# adc_board.net
KiCad netlist of a schematic drawn in EAGLE
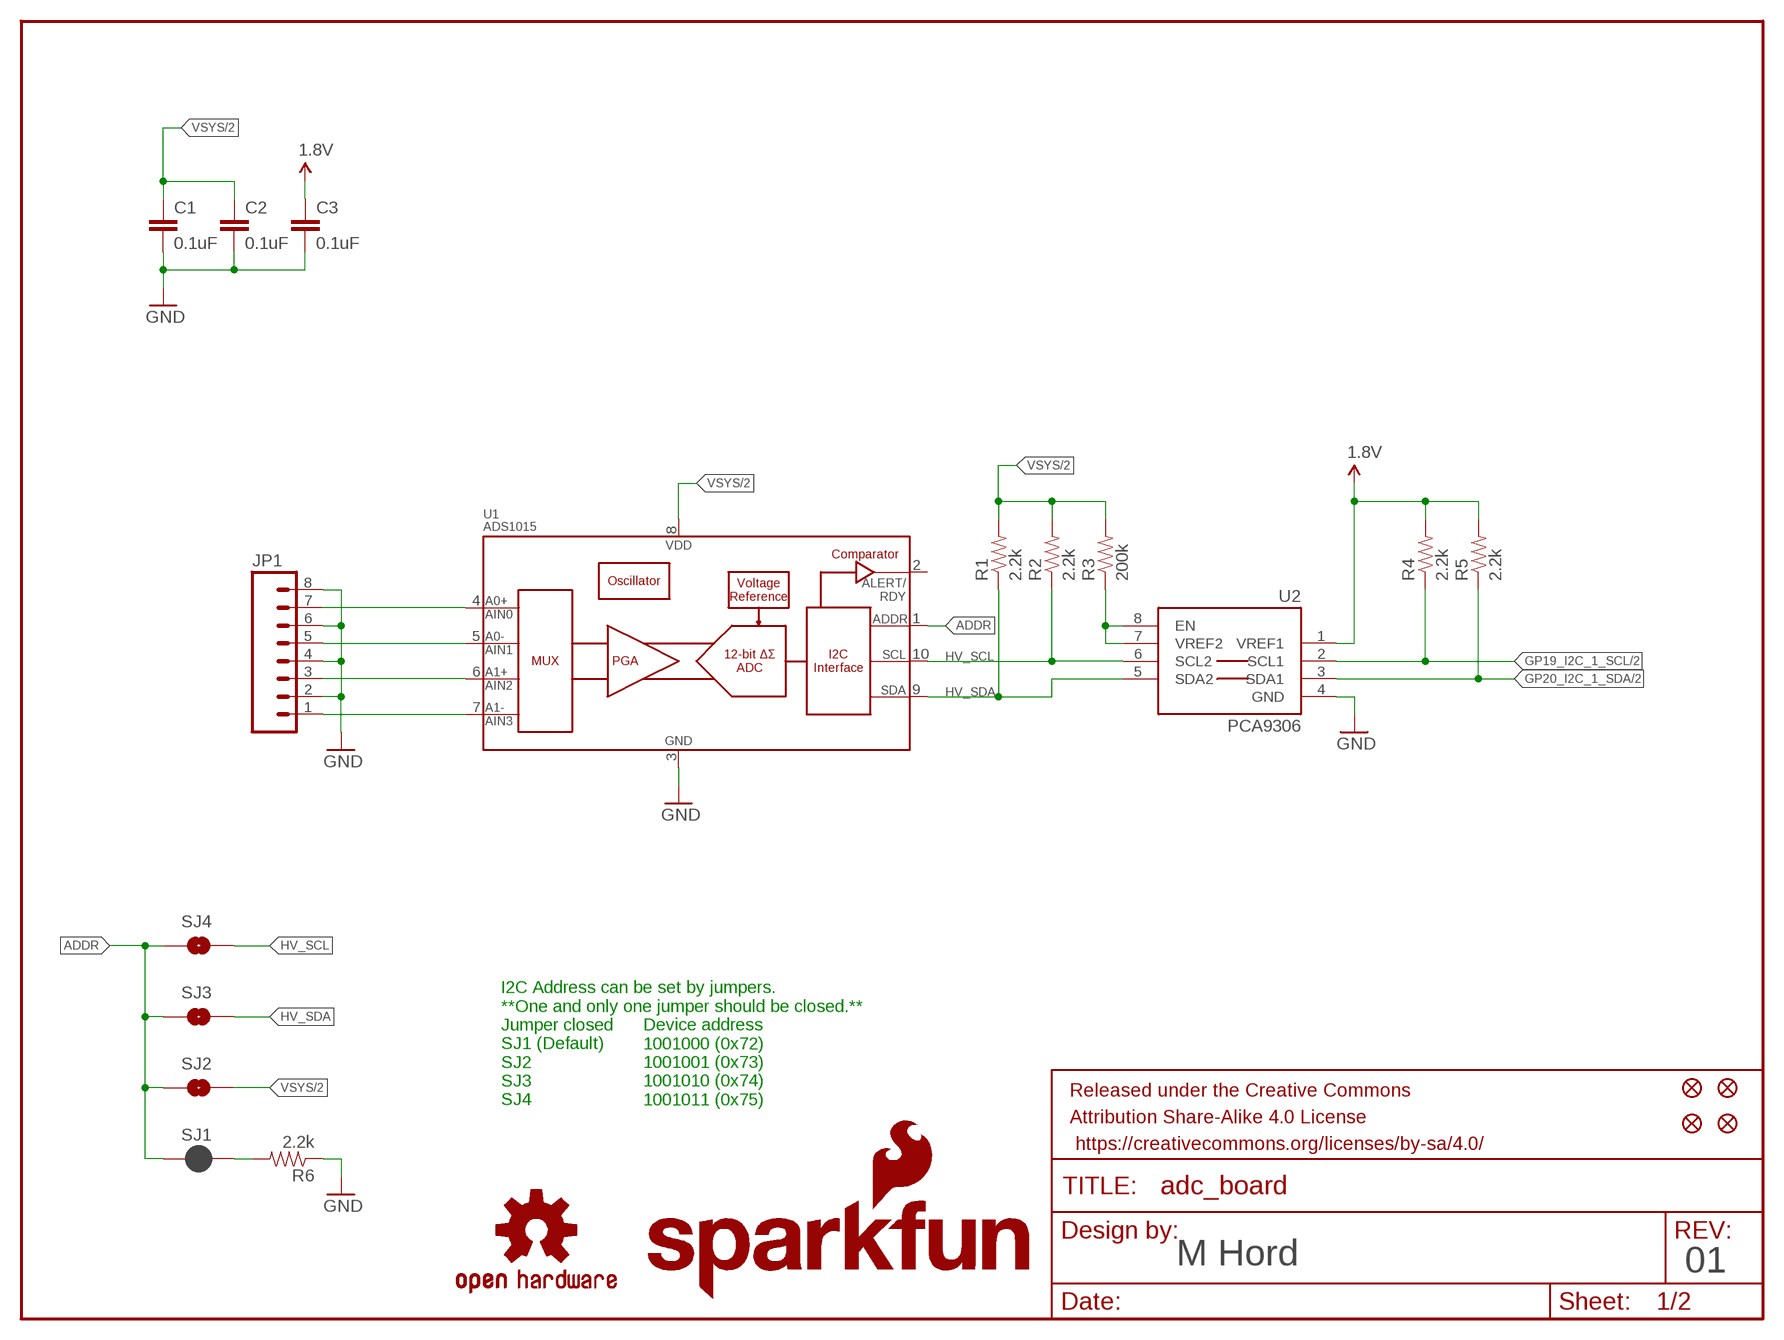
[diagram p0: schematic, sheet 1]
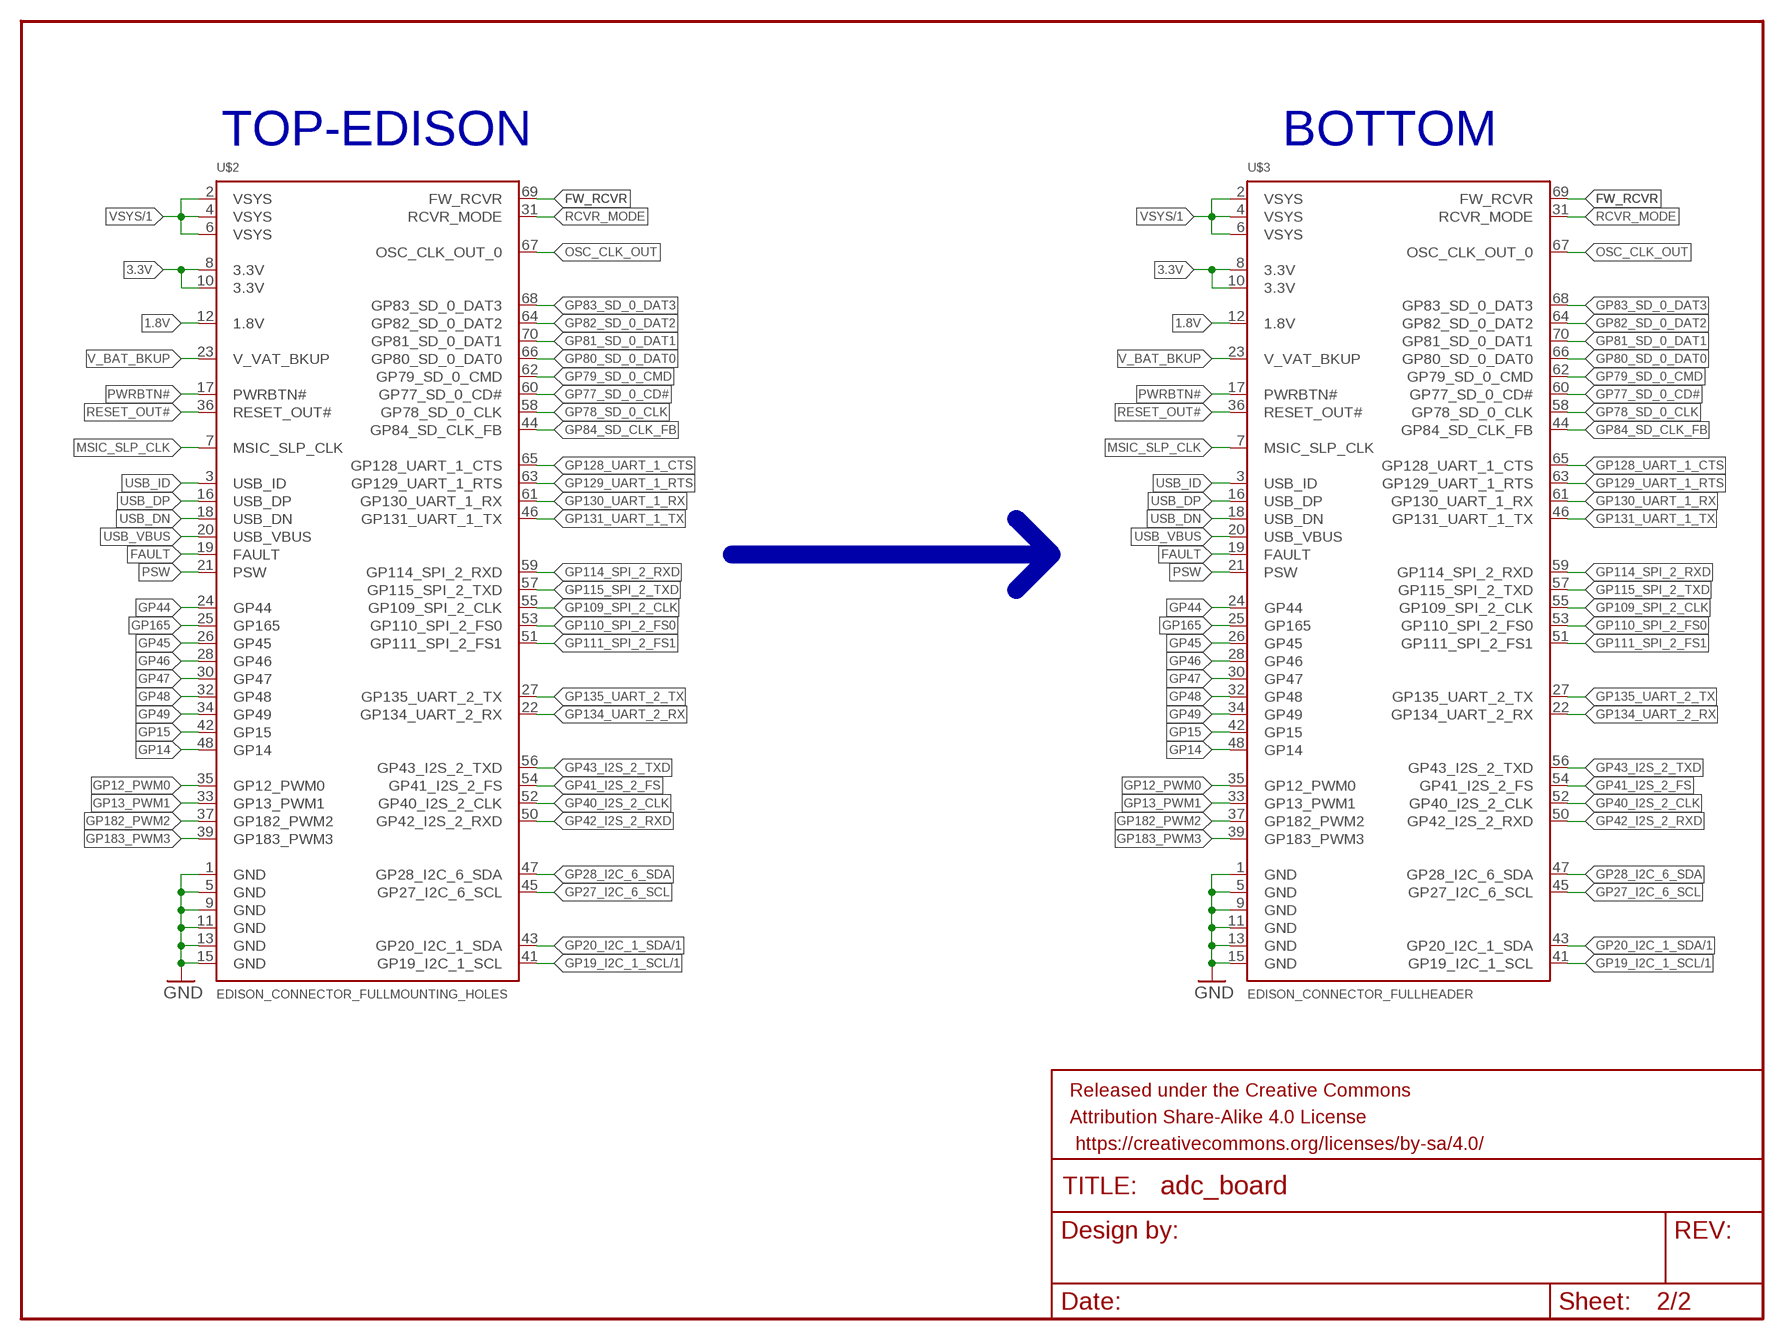
[diagram p1: schematic, sheet 2]

(export (version "E")
  (design (tool "Eeschema 10.0.6"))
  (components
    (comp (ref "C1")
      (value "0.1uF")
      (footprint "eagle-import:0603-CAP")
      (libsource (lib "eagle-import") (part "0.1UF-25V(+80/-20%)(0603)"))
    )
    (comp (ref "C2")
      (value "0.1uF")
      (footprint "eagle-import:0603-CAP")
      (libsource (lib "eagle-import") (part "0.1UF-25V(+80/-20%)(0603)"))
    )
    (comp (ref "C3")
      (value "0.1uF")
      (footprint "eagle-import:0603-CAP")
      (libsource (lib "eagle-import") (part "0.1UF-25V(+80/-20%)(0603)"))
    )
    (comp (ref "FID1")
      (value "FIDUCIAL1X2")
      (footprint "eagle-import:FIDUCIAL-1X2")
      (libsource (lib "eagle-import") (part "FIDUCIAL1X2"))
    )
    (comp (ref "FID2")
      (value "FIDUCIAL1X2")
      (footprint "eagle-import:FIDUCIAL-1X2")
      (libsource (lib "eagle-import") (part "FIDUCIAL1X2"))
    )
    (comp (ref "FID3")
      (value "FIDUCIAL1X2")
      (footprint "eagle-import:FIDUCIAL-1X2")
      (libsource (lib "eagle-import") (part "FIDUCIAL1X2"))
    )
    (comp (ref "FID4")
      (value "FIDUCIAL1X2")
      (footprint "eagle-import:FIDUCIAL-1X2")
      (libsource (lib "eagle-import") (part "FIDUCIAL1X2"))
    )
    (comp (ref "FRAME1")
      (value "FRAME-LETTER")
      (footprint "eagle-import:CREATIVE_COMMONS")
      (libsource (lib "eagle-import") (part "FRAME-LETTER"))
    )
    (comp (ref "JP1")
      (value "M081X08")
      (footprint "eagle-import:1X08")
      (libsource (lib "eagle-import") (part "M081X08"))
    )
    (comp (ref "LOGO1")
      (value "SFE_LOGO_NAME_FLAME.1_INCH")
      (footprint "eagle-import:SFE_LOGO_NAME_FLAME_.1")
      (libsource (lib "eagle-import") (part "SFE_LOGO_NAME_FLAME.1_INCH"))
    )
    (comp (ref "LOGO2")
      (value "OSHW-LOGOS")
      (footprint "eagle-import:OSHW-LOGO-S")
      (libsource (lib "eagle-import") (part "OSHW-LOGOS"))
    )
    (comp (ref "LOGO3")
      (value "SFE_LOGO_NAME_FLAME.1_INCH")
      (footprint "eagle-import:SFE_LOGO_NAME_FLAME_.1")
      (libsource (lib "eagle-import") (part "SFE_LOGO_NAME_FLAME.1_INCH"))
    )
    (comp (ref "LOGO4")
      (value "OSHW-LOGOS")
      (footprint "eagle-import:OSHW-LOGO-S")
      (libsource (lib "eagle-import") (part "OSHW-LOGOS"))
    )
    (comp (ref "R1")
      (value "2.2k")
      (footprint "eagle-import:0603-RES")
      (libsource (lib "eagle-import") (part "2.2KOHM1/10W1%(0603)"))
    )
    (comp (ref "R2")
      (value "2.2k")
      (footprint "eagle-import:0603-RES")
      (libsource (lib "eagle-import") (part "2.2KOHM1/10W1%(0603)"))
    )
    (comp (ref "R3")
      (value "200k")
      (footprint "eagle-import:0603-RES")
      (libsource (lib "eagle-import") (part "200KOHM1/10W1%(0603)200K"))
    )
    (comp (ref "R4")
      (value "2.2k")
      (footprint "eagle-import:0603-RES")
      (libsource (lib "eagle-import") (part "2.2KOHM1/10W1%(0603)"))
    )
    (comp (ref "R5")
      (value "2.2k")
      (footprint "eagle-import:0603-RES")
      (libsource (lib "eagle-import") (part "2.2KOHM1/10W1%(0603)"))
    )
    (comp (ref "R6")
      (value "2.2k")
      (footprint "eagle-import:0603-RES")
      (libsource (lib "eagle-import") (part "2.2KOHM1/10W1%(0603)"))
    )
    (comp (ref "SJ1")
      (value "JUMPER-PAD-2-NC_BY_PASTE")
      (footprint "eagle-import:PAD-JUMPER-2-NC_BY_PASTE_YES_SILK")
      (libsource (lib "eagle-import") (part "JUMPER-PAD-2-NC_BY_PASTE"))
    )
    (comp (ref "SJ2")
      (value "JUMPER-PAD-2-NOYES_SILK")
      (footprint "eagle-import:PAD-JUMPER-2-NO_YES_SILK")
      (libsource (lib "eagle-import") (part "JUMPER-PAD-2-NOYES_SILK"))
    )
    (comp (ref "SJ3")
      (value "JUMPER-PAD-2-NOYES_SILK")
      (footprint "eagle-import:PAD-JUMPER-2-NO_YES_SILK")
      (libsource (lib "eagle-import") (part "JUMPER-PAD-2-NOYES_SILK"))
    )
    (comp (ref "SJ4")
      (value "JUMPER-PAD-2-NOYES_SILK")
      (footprint "eagle-import:PAD-JUMPER-2-NO_YES_SILK")
      (libsource (lib "eagle-import") (part "JUMPER-PAD-2-NOYES_SILK"))
    )
    (comp (ref "U1")
      (value "ADS1015")
      (footprint "eagle-import:MSOP10")
      (libsource (lib "eagle-import") (part "ADS1015"))
    )
    (comp (ref "U2")
      (value "PCA9306")
      (footprint "eagle-import:PCA9306DC-1_1")
      (libsource (lib "eagle-import") (part "PCA9306PCA9306DC-1{colon}1"))
    )
    (comp (ref "FRAME2")
      (value "FRAME-LETTER")
      (footprint "eagle-import:CREATIVE_COMMONS")
      (libsource (lib "eagle-import") (part "FRAME-LETTER"))
    )
    (comp (ref "U$2")
      (value "EDISON_CONNECTOR_FULLMOUNTING_HOLES")
      (footprint "eagle-import:EDISON_DAUGHTER")
      (libsource (lib "eagle-import") (part "EDISON_CONNECTOR_FULLMOUNTING_HOLES"))
    )
    (comp (ref "U$3")
      (value "EDISON_CONNECTOR_FULLHEADER")
      (footprint "eagle-import:DF40C-70DP-0.4(51)")
      (libsource (lib "eagle-import") (part "EDISON_CONNECTOR_FULLHEADER"))
    )
  )
  (nets
    (net (code "1") (name "1.8V") (class "Default")
      (node (ref "C3") (pin "1") (pinfunction "1_1") (pintype "passive"))
      (node (ref "R4") (pin "2") (pinfunction "2_2") (pintype "passive"))
      (node (ref "R5") (pin "2") (pinfunction "2_2") (pintype "passive"))
      (node (ref "U$2") (pin "12") (pinfunction "1.8V_12") (pintype "bidirectional"))
      (node (ref "U$3") (pin "12") (pinfunction "1.8V_12") (pintype "bidirectional"))
      (node (ref "U2") (pin "1") (pinfunction "VREF1_1") (pintype "bidirectional"))
    )
    (net (code "2") (name "3.3V") (class "Default")
      (node (ref "U$2") (pin "10") (pinfunction "3.3V_10") (pintype "bidirectional"))
      (node (ref "U$2") (pin "8") (pinfunction "3.3V_8") (pintype "bidirectional"))
      (node (ref "U$3") (pin "10") (pinfunction "3.3V_10") (pintype "bidirectional"))
      (node (ref "U$3") (pin "8") (pinfunction "3.3V_8") (pintype "bidirectional"))
    )
    (net (code "3") (name "ADDR") (class "Default")
      (node (ref "SJ1") (pin "1") (pinfunction "1_1") (pintype "passive"))
      (node (ref "SJ2") (pin "1") (pinfunction "1_1") (pintype "passive"))
      (node (ref "SJ3") (pin "1") (pinfunction "1_1") (pintype "passive"))
      (node (ref "SJ4") (pin "1") (pinfunction "1_1") (pintype "passive"))
      (node (ref "U1") (pin "1") (pinfunction "ADDR_1") (pintype "bidirectional"))
    )
    (net (code "4") (name "FAULT") (class "Default")
      (node (ref "U$2") (pin "19") (pinfunction "FAULT_19") (pintype "bidirectional"))
      (node (ref "U$3") (pin "19") (pinfunction "FAULT_19") (pintype "bidirectional"))
    )
    (net (code "5") (name "FW_RCVR") (class "Default")
      (node (ref "U$2") (pin "69") (pinfunction "FW_RCVR_69") (pintype "bidirectional"))
      (node (ref "U$3") (pin "69") (pinfunction "FW_RCVR_69") (pintype "bidirectional"))
    )
    (net (code "6") (name "GND") (class "Default")
      (node (ref "C1") (pin "2") (pinfunction "2_2") (pintype "passive"))
      (node (ref "C2") (pin "2") (pinfunction "2_2") (pintype "passive"))
      (node (ref "C3") (pin "2") (pinfunction "2_2") (pintype "passive"))
      (node (ref "JP1") (pin "2") (pinfunction "2_2") (pintype "passive"))
      (node (ref "JP1") (pin "4") (pinfunction "4_4") (pintype "passive"))
      (node (ref "JP1") (pin "6") (pinfunction "6_6") (pintype "passive"))
      (node (ref "JP1") (pin "8") (pinfunction "8_8") (pintype "passive"))
      (node (ref "R6") (pin "1") (pinfunction "1_1") (pintype "passive"))
      (node (ref "U$2") (pin "1") (pinfunction "GND_1") (pintype "bidirectional"))
      (node (ref "U$2") (pin "11") (pinfunction "GND_11") (pintype "bidirectional"))
      (node (ref "U$2") (pin "13") (pinfunction "GND_13") (pintype "bidirectional"))
      (node (ref "U$2") (pin "15") (pinfunction "GND_15") (pintype "bidirectional"))
      (node (ref "U$2") (pin "5") (pinfunction "GND_5") (pintype "bidirectional"))
      (node (ref "U$2") (pin "9") (pinfunction "GND_9") (pintype "bidirectional"))
      (node (ref "U$3") (pin "1") (pinfunction "GND_1") (pintype "bidirectional"))
      (node (ref "U$3") (pin "11") (pinfunction "GND_11") (pintype "bidirectional"))
      (node (ref "U$3") (pin "13") (pinfunction "GND_13") (pintype "bidirectional"))
      (node (ref "U$3") (pin "15") (pinfunction "GND_15") (pintype "bidirectional"))
      (node (ref "U$3") (pin "5") (pinfunction "GND_5") (pintype "bidirectional"))
      (node (ref "U$3") (pin "9") (pinfunction "GND_9") (pintype "bidirectional"))
      (node (ref "U1") (pin "3") (pinfunction "VSS_3") (pintype "bidirectional"))
      (node (ref "U2") (pin "4") (pinfunction "GND_4") (pintype "bidirectional"))
    )
    (net (code "7") (name "GP12_PWM0") (class "Default")
      (node (ref "U$2") (pin "35") (pinfunction "GP12_PWM0_35") (pintype "bidirectional"))
      (node (ref "U$3") (pin "35") (pinfunction "GP12_PWM0_35") (pintype "bidirectional"))
    )
    (net (code "8") (name "GP13_PWM1") (class "Default")
      (node (ref "U$2") (pin "33") (pinfunction "GP13_PWM1_33") (pintype "bidirectional"))
      (node (ref "U$3") (pin "33") (pinfunction "GP13_PWM1_33") (pintype "bidirectional"))
    )
    (net (code "9") (name "GP14") (class "Default")
      (node (ref "U$2") (pin "48") (pinfunction "GP14_48") (pintype "bidirectional"))
      (node (ref "U$3") (pin "48") (pinfunction "GP14_48") (pintype "bidirectional"))
    )
    (net (code "10") (name "GP15") (class "Default")
      (node (ref "U$2") (pin "42") (pinfunction "GP15_42") (pintype "bidirectional"))
      (node (ref "U$3") (pin "42") (pinfunction "GP15_42") (pintype "bidirectional"))
    )
    (net (code "11") (name "GP19_I2C_1_SCL") (class "Default")
      (node (ref "R4") (pin "1") (pinfunction "1_1") (pintype "passive"))
      (node (ref "U$2") (pin "41") (pinfunction "GP19_I2C_1_SCL_41") (pintype "bidirectional"))
      (node (ref "U$3") (pin "41") (pinfunction "GP19_I2C_1_SCL_41") (pintype "bidirectional"))
      (node (ref "U2") (pin "2") (pinfunction "SCL1_2") (pintype "bidirectional"))
    )
    (net (code "12") (name "GP20_I2C_1_SDA") (class "Default")
      (node (ref "R5") (pin "1") (pinfunction "1_1") (pintype "passive"))
      (node (ref "U$2") (pin "43") (pinfunction "GP20_I2C_1_SDA_43") (pintype "bidirectional"))
      (node (ref "U$3") (pin "43") (pinfunction "GP20_I2C_1_SDA_43") (pintype "bidirectional"))
      (node (ref "U2") (pin "3") (pinfunction "SDA1_3") (pintype "bidirectional"))
    )
    (net (code "13") (name "GP27_I2C_6_SCL") (class "Default")
      (node (ref "U$2") (pin "45") (pinfunction "GP27_I2C_6_SCL_45") (pintype "bidirectional"))
      (node (ref "U$3") (pin "45") (pinfunction "GP27_I2C_6_SCL_45") (pintype "bidirectional"))
    )
    (net (code "14") (name "GP28_I2C_6_SDA") (class "Default")
      (node (ref "U$2") (pin "47") (pinfunction "GP28_I2C_6_SDA_47") (pintype "bidirectional"))
      (node (ref "U$3") (pin "47") (pinfunction "GP28_I2C_6_SDA_47") (pintype "bidirectional"))
    )
    (net (code "15") (name "GP40_I2S_2_CLK") (class "Default")
      (node (ref "U$2") (pin "52") (pinfunction "GP40_I2S_2_CLK_52") (pintype "bidirectional"))
      (node (ref "U$3") (pin "52") (pinfunction "GP40_I2S_2_CLK_52") (pintype "bidirectional"))
    )
    (net (code "16") (name "GP41_I2S_2_FS") (class "Default")
      (node (ref "U$2") (pin "54") (pinfunction "GP41_I2S_2_FS_54") (pintype "bidirectional"))
      (node (ref "U$3") (pin "54") (pinfunction "GP41_I2S_2_FS_54") (pintype "bidirectional"))
    )
    (net (code "17") (name "GP42_I2S_2_RXD") (class "Default")
      (node (ref "U$2") (pin "50") (pinfunction "GP42_I2S_2_RXD_50") (pintype "bidirectional"))
      (node (ref "U$3") (pin "50") (pinfunction "GP42_I2S_2_RXD_50") (pintype "bidirectional"))
    )
    (net (code "18") (name "GP43_I2S_2_TXD") (class "Default")
      (node (ref "U$2") (pin "56") (pinfunction "GP43_I2S_2_TXD_56") (pintype "bidirectional"))
      (node (ref "U$3") (pin "56") (pinfunction "GP43_I2S_2_TXD_56") (pintype "bidirectional"))
    )
    (net (code "19") (name "GP44") (class "Default")
      (node (ref "U$2") (pin "24") (pinfunction "GP44_24") (pintype "bidirectional"))
      (node (ref "U$3") (pin "24") (pinfunction "GP44_24") (pintype "bidirectional"))
    )
    (net (code "20") (name "GP45") (class "Default")
      (node (ref "U$2") (pin "26") (pinfunction "GP45_26") (pintype "bidirectional"))
      (node (ref "U$3") (pin "26") (pinfunction "GP45_26") (pintype "bidirectional"))
    )
    (net (code "21") (name "GP46") (class "Default")
      (node (ref "U$2") (pin "28") (pinfunction "GP46_28") (pintype "bidirectional"))
      (node (ref "U$3") (pin "28") (pinfunction "GP46_28") (pintype "bidirectional"))
    )
    (net (code "22") (name "GP47") (class "Default")
      (node (ref "U$2") (pin "30") (pinfunction "GP47_30") (pintype "bidirectional"))
      (node (ref "U$3") (pin "30") (pinfunction "GP47_30") (pintype "bidirectional"))
    )
    (net (code "23") (name "GP48") (class "Default")
      (node (ref "U$2") (pin "32") (pinfunction "GP48_32") (pintype "bidirectional"))
      (node (ref "U$3") (pin "32") (pinfunction "GP48_32") (pintype "bidirectional"))
    )
    (net (code "24") (name "GP49") (class "Default")
      (node (ref "U$2") (pin "34") (pinfunction "GP49_34") (pintype "bidirectional"))
      (node (ref "U$3") (pin "34") (pinfunction "GP49_34") (pintype "bidirectional"))
    )
    (net (code "25") (name "GP77_SD_0_CD#") (class "Default")
      (node (ref "U$2") (pin "60") (pinfunction "GP77_SD_0_CD#_60") (pintype "bidirectional"))
      (node (ref "U$3") (pin "60") (pinfunction "GP77_SD_0_CD#_60") (pintype "bidirectional"))
    )
    (net (code "26") (name "GP78_SD_0_CLK") (class "Default")
      (node (ref "U$2") (pin "58") (pinfunction "GP78_SD_0_CLK_58") (pintype "bidirectional"))
      (node (ref "U$3") (pin "58") (pinfunction "GP78_SD_0_CLK_58") (pintype "bidirectional"))
    )
    (net (code "27") (name "GP79_SD_0_CMD") (class "Default")
      (node (ref "U$2") (pin "62") (pinfunction "GP79_SD_0_CMD_62") (pintype "bidirectional"))
      (node (ref "U$3") (pin "62") (pinfunction "GP79_SD_0_CMD_62") (pintype "bidirectional"))
    )
    (net (code "28") (name "GP80_SD_0_DAT0") (class "Default")
      (node (ref "U$2") (pin "66") (pinfunction "GP80_SD_0_DAT0_66") (pintype "bidirectional"))
      (node (ref "U$3") (pin "66") (pinfunction "GP80_SD_0_DAT0_66") (pintype "bidirectional"))
    )
    (net (code "29") (name "GP81_SD_0_DAT1") (class "Default")
      (node (ref "U$2") (pin "70") (pinfunction "GP81_SD_0_DAT1_70") (pintype "bidirectional"))
      (node (ref "U$3") (pin "70") (pinfunction "GP81_SD_0_DAT1_70") (pintype "bidirectional"))
    )
    (net (code "30") (name "GP82_SD_0_DAT2") (class "Default")
      (node (ref "U$2") (pin "64") (pinfunction "GP82_SD_0_DAT2_64") (pintype "bidirectional"))
      (node (ref "U$3") (pin "64") (pinfunction "GP82_SD_0_DAT2_64") (pintype "bidirectional"))
    )
    (net (code "31") (name "GP83_SD_0_DAT3") (class "Default")
      (node (ref "U$2") (pin "68") (pinfunction "GP83_SD_0_DAT3_68") (pintype "bidirectional"))
      (node (ref "U$3") (pin "68") (pinfunction "GP83_SD_0_DAT3_68") (pintype "bidirectional"))
    )
    (net (code "32") (name "GP84_SD_CLK_FB") (class "Default")
      (node (ref "U$2") (pin "44") (pinfunction "GP84_SD_CLK_FB_44") (pintype "bidirectional"))
      (node (ref "U$3") (pin "44") (pinfunction "GP84_SD_CLK_FB_44") (pintype "bidirectional"))
    )
    (net (code "33") (name "GP109_SPI_2_CLK") (class "Default")
      (node (ref "U$2") (pin "55") (pinfunction "GP109_SPI_2_CLK_55") (pintype "bidirectional"))
      (node (ref "U$3") (pin "55") (pinfunction "GP109_SPI_2_CLK_55") (pintype "bidirectional"))
    )
    (net (code "34") (name "GP110_SPI_2_FS0") (class "Default")
      (node (ref "U$2") (pin "53") (pinfunction "GP110_SPI_2_FS0_53") (pintype "bidirectional"))
      (node (ref "U$3") (pin "53") (pinfunction "GP110_SPI_2_FS0_53") (pintype "bidirectional"))
    )
    (net (code "35") (name "GP111_SPI_2_FS1") (class "Default")
      (node (ref "U$2") (pin "51") (pinfunction "GP111_SPI_2_FS1_51") (pintype "bidirectional"))
      (node (ref "U$3") (pin "51") (pinfunction "GP111_SPI_2_FS1_51") (pintype "bidirectional"))
    )
    (net (code "36") (name "GP114_SPI_2_RXD") (class "Default")
      (node (ref "U$2") (pin "59") (pinfunction "GP114_SPI_2_RXD_59") (pintype "bidirectional"))
      (node (ref "U$3") (pin "59") (pinfunction "GP114_SPI_2_RXD_59") (pintype "bidirectional"))
    )
    (net (code "37") (name "GP115_SPI_2_TXD") (class "Default")
      (node (ref "U$2") (pin "57") (pinfunction "GP115_SPI_2_TXD_57") (pintype "bidirectional"))
      (node (ref "U$3") (pin "57") (pinfunction "GP115_SPI_2_TXD_57") (pintype "bidirectional"))
    )
    (net (code "38") (name "GP128_UART_1_CTS") (class "Default")
      (node (ref "U$2") (pin "65") (pinfunction "GP128_UART_1_CTS_65") (pintype "bidirectional"))
      (node (ref "U$3") (pin "65") (pinfunction "GP128_UART_1_CTS_65") (pintype "bidirectional"))
    )
    (net (code "39") (name "GP129_UART_1_RTS") (class "Default")
      (node (ref "U$2") (pin "63") (pinfunction "GP129_UART_1_RTS_63") (pintype "bidirectional"))
      (node (ref "U$3") (pin "63") (pinfunction "GP129_UART_1_RTS_63") (pintype "bidirectional"))
    )
    (net (code "40") (name "GP130_UART_1_RX") (class "Default")
      (node (ref "U$2") (pin "61") (pinfunction "GP130_UART_1_RX_61") (pintype "bidirectional"))
      (node (ref "U$3") (pin "61") (pinfunction "GP130_UART_1_RX_61") (pintype "bidirectional"))
    )
    (net (code "41") (name "GP131_UART_1_TX") (class "Default")
      (node (ref "U$2") (pin "46") (pinfunction "GP131_UART_1_TX_46") (pintype "bidirectional"))
      (node (ref "U$3") (pin "46") (pinfunction "GP131_UART_1_TX_46") (pintype "bidirectional"))
    )
    (net (code "42") (name "GP134_UART_2_RX") (class "Default")
      (node (ref "U$2") (pin "22") (pinfunction "GP134_UART_2_RX_22") (pintype "bidirectional"))
      (node (ref "U$3") (pin "22") (pinfunction "GP134_UART_2_RX_22") (pintype "bidirectional"))
    )
    (net (code "43") (name "GP135_UART_2_TX") (class "Default")
      (node (ref "U$2") (pin "27") (pinfunction "GP135_UART_2_TX_27") (pintype "bidirectional"))
      (node (ref "U$3") (pin "27") (pinfunction "GP135_UART_2_TX_27") (pintype "bidirectional"))
    )
    (net (code "44") (name "GP165") (class "Default")
      (node (ref "U$2") (pin "25") (pinfunction "GP165_25") (pintype "bidirectional"))
      (node (ref "U$3") (pin "25") (pinfunction "GP165_25") (pintype "bidirectional"))
    )
    (net (code "45") (name "GP182_PWM2") (class "Default")
      (node (ref "U$2") (pin "37") (pinfunction "GP182_PWM2_37") (pintype "bidirectional"))
      (node (ref "U$3") (pin "37") (pinfunction "GP182_PWM2_37") (pintype "bidirectional"))
    )
    (net (code "46") (name "GP183_PWM3") (class "Default")
      (node (ref "U$2") (pin "39") (pinfunction "GP183_PWM3_39") (pintype "bidirectional"))
      (node (ref "U$3") (pin "39") (pinfunction "GP183_PWM3_39") (pintype "bidirectional"))
    )
    (net (code "47") (name "HV_SCL") (class "Default")
      (node (ref "R2") (pin "1") (pinfunction "1_1") (pintype "passive"))
      (node (ref "SJ4") (pin "2") (pinfunction "2_2") (pintype "passive"))
      (node (ref "U1") (pin "10") (pinfunction "SCL_10") (pintype "bidirectional"))
      (node (ref "U2") (pin "6") (pinfunction "SCL2_6") (pintype "bidirectional"))
    )
    (net (code "48") (name "HV_SDA") (class "Default")
      (node (ref "R1") (pin "1") (pinfunction "1_1") (pintype "passive"))
      (node (ref "SJ3") (pin "2") (pinfunction "2_2") (pintype "passive"))
      (node (ref "U1") (pin "9") (pinfunction "SDA_9") (pintype "bidirectional"))
      (node (ref "U2") (pin "5") (pinfunction "SDA2_5") (pintype "bidirectional"))
    )
    (net (code "49") (name "MSIC_SLP_CLK") (class "Default")
      (node (ref "U$2") (pin "7") (pinfunction "MSIC_SLP_CLK_7") (pintype "bidirectional"))
      (node (ref "U$3") (pin "7") (pinfunction "MSIC_SLP_CLK_7") (pintype "bidirectional"))
    )
    (net (code "50") (name "Net-(R6-Pad2)") (class "Default")
      (node (ref "R6") (pin "2") (pinfunction "2_2") (pintype "passive"))
      (node (ref "SJ1") (pin "2") (pinfunction "2_2") (pintype "passive"))
    )
    (net (code "51") (name "Net-(U1-AIN0)") (class "Default")
      (node (ref "JP1") (pin "7") (pinfunction "7_7") (pintype "passive"))
      (node (ref "U1") (pin "4") (pinfunction "AIN0_4") (pintype "bidirectional"))
    )
    (net (code "52") (name "Net-(U1-AIN1)") (class "Default")
      (node (ref "JP1") (pin "5") (pinfunction "5_5") (pintype "passive"))
      (node (ref "U1") (pin "5") (pinfunction "AIN1_5") (pintype "bidirectional"))
    )
    (net (code "53") (name "Net-(U1-AIN2)") (class "Default")
      (node (ref "JP1") (pin "3") (pinfunction "3_3") (pintype "passive"))
      (node (ref "U1") (pin "6") (pinfunction "AIN2_6") (pintype "bidirectional"))
    )
    (net (code "54") (name "Net-(U1-AIN3)") (class "Default")
      (node (ref "JP1") (pin "1") (pinfunction "1_1") (pintype "passive"))
      (node (ref "U1") (pin "7") (pinfunction "AIN3_7") (pintype "bidirectional"))
    )
    (net (code "55") (name "Net-(U2-EN)") (class "Default")
      (node (ref "R3") (pin "1") (pinfunction "1_1") (pintype "passive"))
      (node (ref "U2") (pin "7") (pinfunction "VREF2_7") (pintype "bidirectional"))
      (node (ref "U2") (pin "8") (pinfunction "EN_8") (pintype "bidirectional"))
    )
    (net (code "56") (name "OSC_CLK_OUT") (class "Default")
      (node (ref "U$2") (pin "67") (pinfunction "OSC_CLK_OUT_0_67") (pintype "bidirectional"))
      (node (ref "U$3") (pin "67") (pinfunction "OSC_CLK_OUT_0_67") (pintype "bidirectional"))
    )
    (net (code "57") (name "PSW") (class "Default")
      (node (ref "U$2") (pin "21") (pinfunction "PSW_21") (pintype "bidirectional"))
      (node (ref "U$3") (pin "21") (pinfunction "PSW_21") (pintype "bidirectional"))
    )
    (net (code "58") (name "PWRBTN#") (class "Default")
      (node (ref "U$2") (pin "17") (pinfunction "PWRBTN#_17") (pintype "bidirectional"))
      (node (ref "U$3") (pin "17") (pinfunction "PWRBTN#_17") (pintype "bidirectional"))
    )
    (net (code "59") (name "RCVR_MODE") (class "Default")
      (node (ref "U$2") (pin "31") (pinfunction "RCVR_MODE_31") (pintype "bidirectional"))
      (node (ref "U$3") (pin "31") (pinfunction "RCVR_MODE_31") (pintype "bidirectional"))
    )
    (net (code "60") (name "RESET_OUT#") (class "Default")
      (node (ref "U$2") (pin "36") (pinfunction "RESET_OUT#_36") (pintype "bidirectional"))
      (node (ref "U$3") (pin "36") (pinfunction "RESET_OUT#_36") (pintype "bidirectional"))
    )
    (net (code "61") (name "USB_DN") (class "Default")
      (node (ref "U$2") (pin "18") (pinfunction "USB_DN_18") (pintype "bidirectional"))
      (node (ref "U$3") (pin "18") (pinfunction "USB_DN_18") (pintype "bidirectional"))
    )
    (net (code "62") (name "USB_DP") (class "Default")
      (node (ref "U$2") (pin "16") (pinfunction "USB_DP_16") (pintype "bidirectional"))
      (node (ref "U$3") (pin "16") (pinfunction "USB_DP_16") (pintype "bidirectional"))
    )
    (net (code "63") (name "USB_ID") (class "Default")
      (node (ref "U$2") (pin "3") (pinfunction "USB_ID_3") (pintype "bidirectional"))
      (node (ref "U$3") (pin "3") (pinfunction "USB_ID_3") (pintype "bidirectional"))
    )
    (net (code "64") (name "USB_VBUS") (class "Default")
      (node (ref "U$2") (pin "20") (pinfunction "USB_VBUS_20") (pintype "bidirectional"))
      (node (ref "U$3") (pin "20") (pinfunction "USB_VBUS_20") (pintype "bidirectional"))
    )
    (net (code "65") (name "VSYS") (class "Default")
      (node (ref "C1") (pin "1") (pinfunction "1_1") (pintype "passive"))
      (node (ref "C2") (pin "1") (pinfunction "1_1") (pintype "passive"))
      (node (ref "R1") (pin "2") (pinfunction "2_2") (pintype "passive"))
      (node (ref "R2") (pin "2") (pinfunction "2_2") (pintype "passive"))
      (node (ref "R3") (pin "2") (pinfunction "2_2") (pintype "passive"))
      (node (ref "SJ2") (pin "2") (pinfunction "2_2") (pintype "passive"))
      (node (ref "U$2") (pin "2") (pinfunction "VSYS_2") (pintype "bidirectional"))
      (node (ref "U$2") (pin "4") (pinfunction "VSYS_4") (pintype "bidirectional"))
      (node (ref "U$2") (pin "6") (pinfunction "VSYS_6") (pintype "bidirectional"))
      (node (ref "U$3") (pin "2") (pinfunction "VSYS_2") (pintype "bidirectional"))
      (node (ref "U$3") (pin "4") (pinfunction "VSYS_4") (pintype "bidirectional"))
      (node (ref "U$3") (pin "6") (pinfunction "VSYS_6") (pintype "bidirectional"))
      (node (ref "U1") (pin "8") (pinfunction "VDD_8") (pintype "bidirectional"))
    )
    (net (code "66") (name "V_BAT_BKUP") (class "Default")
      (node (ref "U$2") (pin "23") (pinfunction "V_VAT_BKUP_23") (pintype "bidirectional"))
      (node (ref "U$3") (pin "23") (pinfunction "V_VAT_BKUP_23") (pintype "bidirectional"))
    )
    (net (code "67") (name "unconnected-(U1-ALERT{slash}RDY-Pad2)") (class "Default")
      (node (ref "U1") (pin "2") (pinfunction "ALERT/RDY_2") (pintype "bidirectional"))
    )
  )
)
